# OV7725.net
KiCad netlist of a schematic drawn in EAGLE
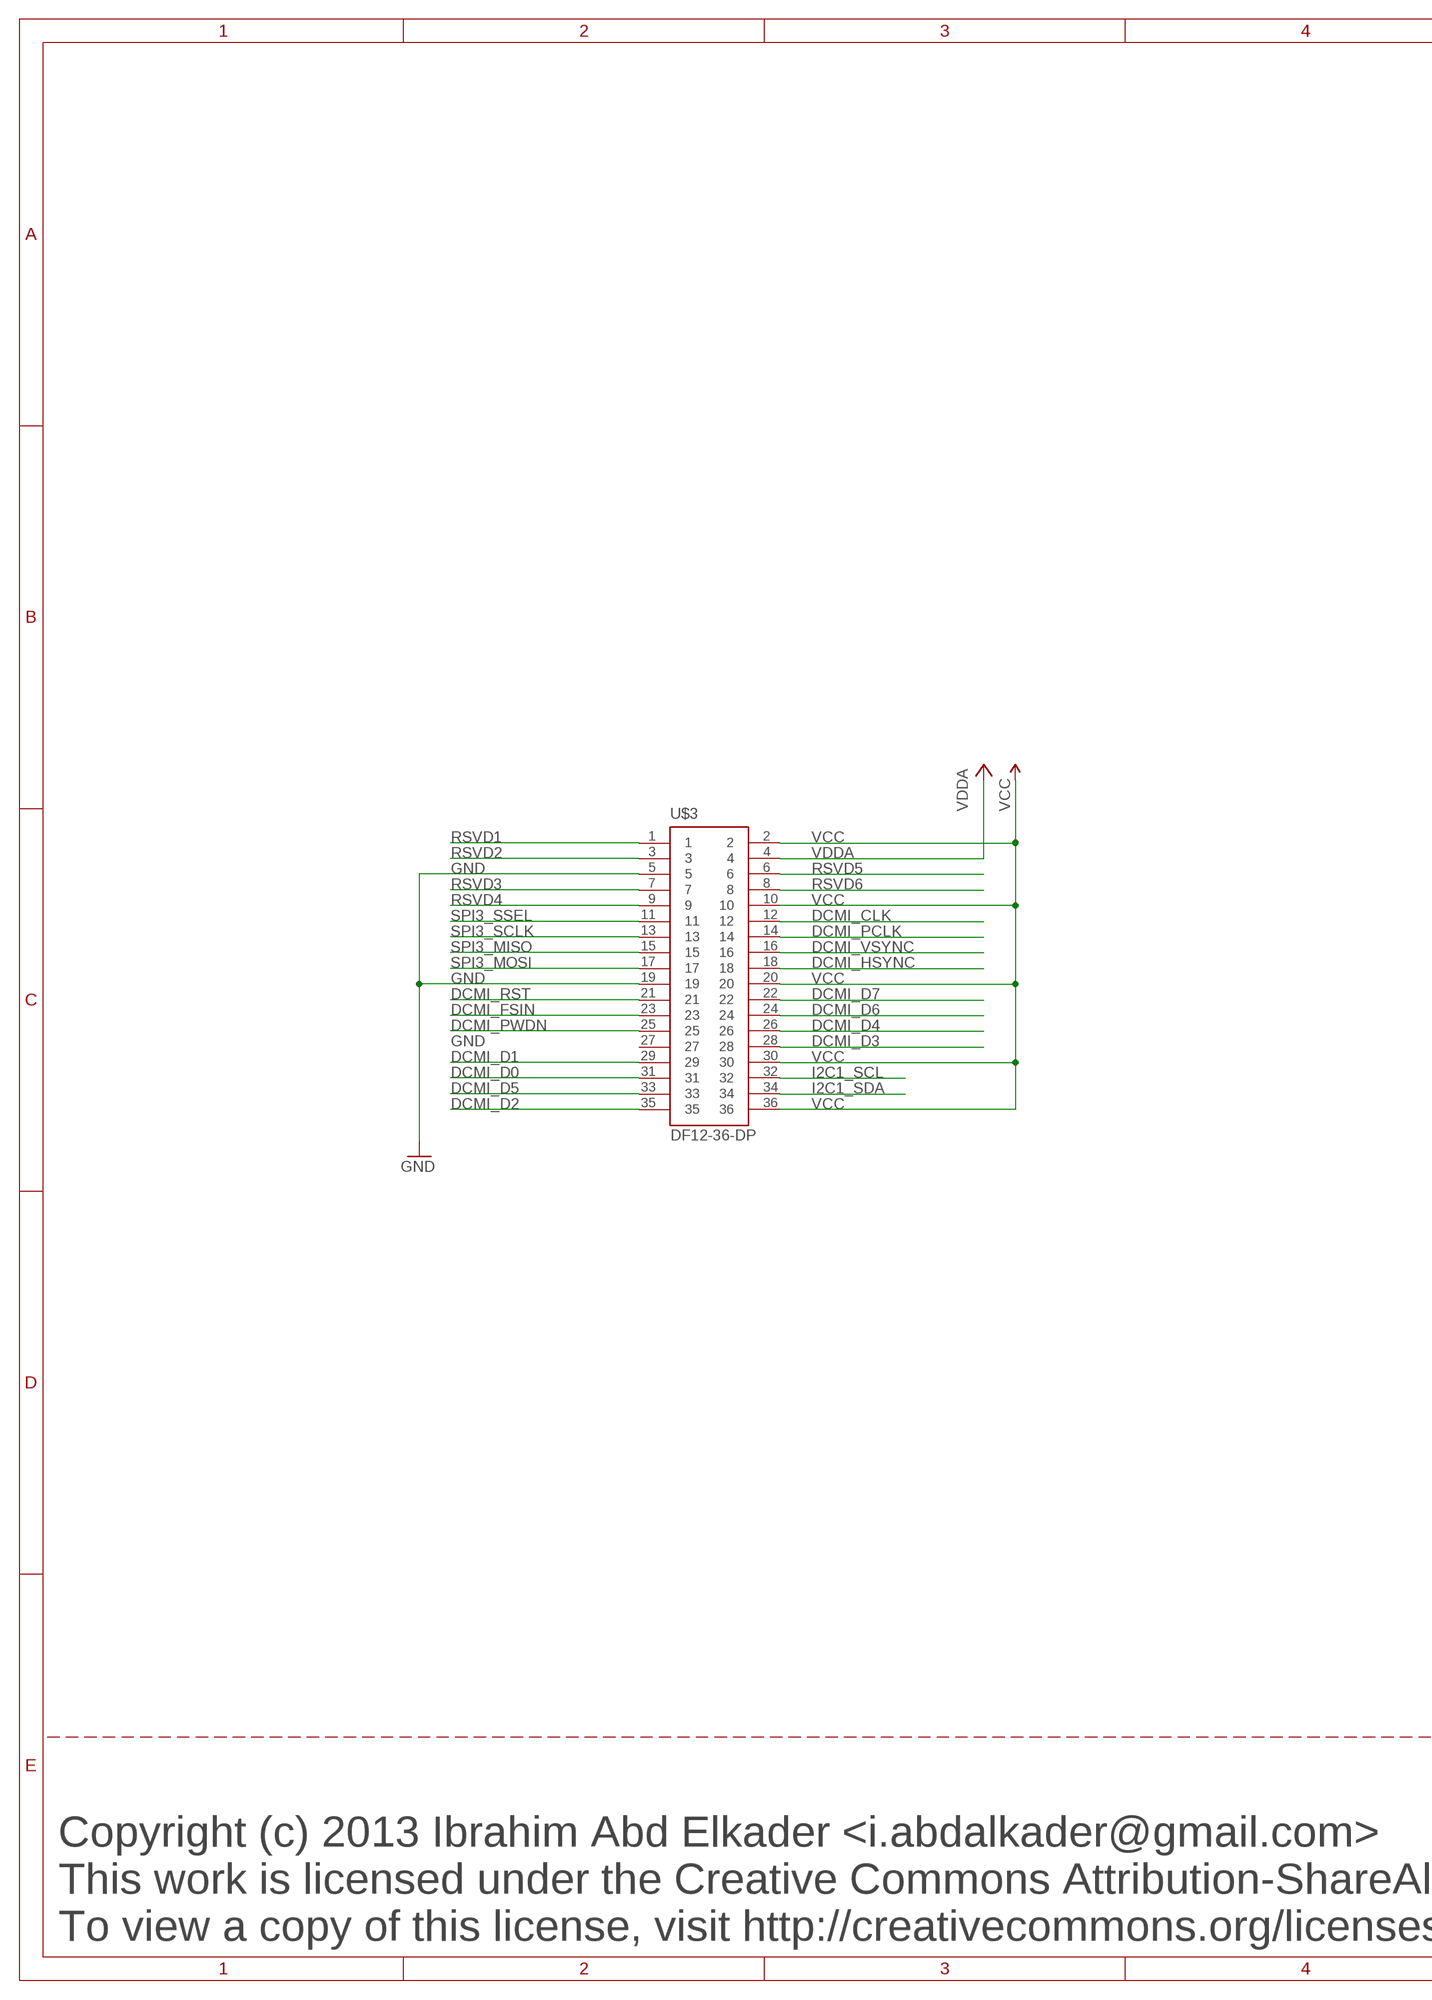
[diagram p0: schematic, sheet 1, part 1 of 2]
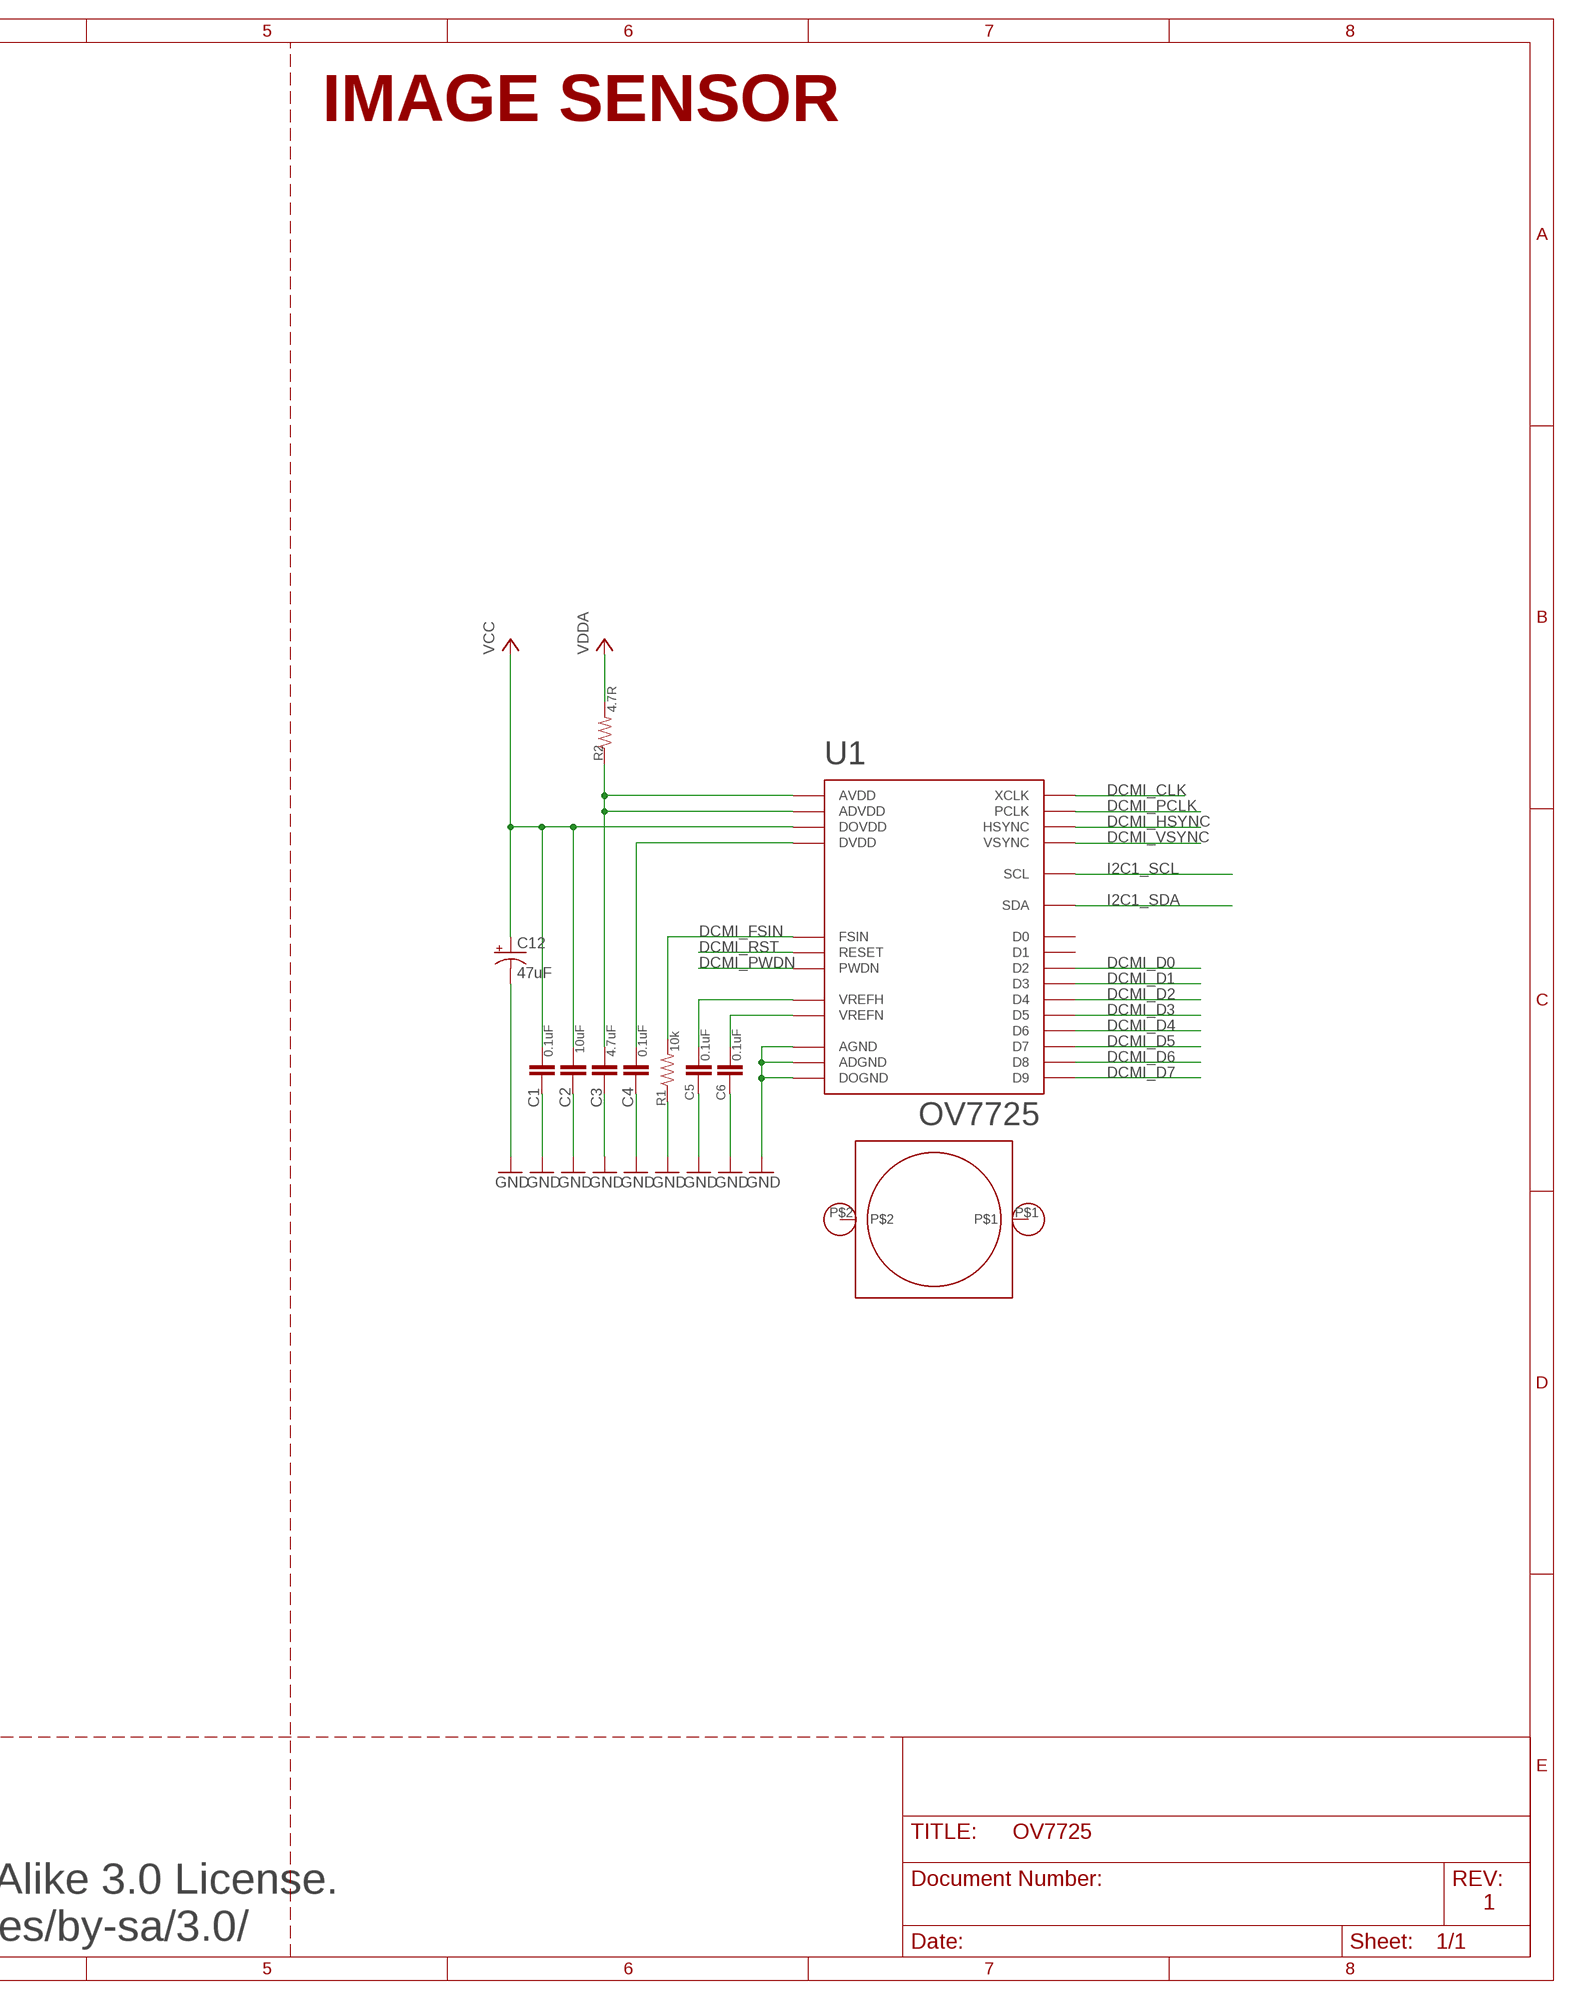
[diagram p1: schematic, sheet 1, part 2 of 2]

(export (version "E")
  (design (tool "Eeschema 10.0.6"))
  (components
    (comp (ref "C1")
      (value "0.1uF")
      (footprint "eagle-import:0603-CAP")
      (libsource (lib "eagle-import") (part "CAP0603-CAP"))
    )
    (comp (ref "C2")
      (value "10uF")
      (footprint "eagle-import:0805")
      (libsource (lib "eagle-import") (part "CAP0805"))
    )
    (comp (ref "C3")
      (value "4.7uF")
      (footprint "eagle-import:0603-CAP")
      (libsource (lib "eagle-import") (part "CAP0603-CAP"))
    )
    (comp (ref "C4")
      (value "0.1uF")
      (footprint "eagle-import:0603-CAP")
      (libsource (lib "eagle-import") (part "CAP0603-CAP"))
    )
    (comp (ref "C5")
      (value "0.1uF")
      (footprint "eagle-import:0603-CAP")
      (libsource (lib "eagle-import") (part "CAP0603-CAP"))
    )
    (comp (ref "C6")
      (value "0.1uF")
      (footprint "eagle-import:0603-CAP")
      (libsource (lib "eagle-import") (part "CAP0603-CAP"))
    )
    (comp (ref "C12")
      (value "47uF")
      (footprint "eagle-import:EIA3216")
      (libsource (lib "eagle-import") (part "CAP_POL1206"))
    )
    (comp (ref "LM1")
      (value "LENSMOUNT20MM")
      (footprint "eagle-import:LENSMOUNT-20MM")
      (libsource (lib "eagle-import") (part "LENSMOUNT20MM"))
    )
    (comp (ref "R1")
      (value "10k")
      (footprint "eagle-import:0603-RES")
      (libsource (lib "eagle-import") (part "RESISTOR0603-RES"))
    )
    (comp (ref "R2")
      (value "4.7R")
      (footprint "eagle-import:0603-RES")
      (libsource (lib "eagle-import") (part "RESISTOR0603-RES"))
    )
    (comp (ref "U$3")
      (value "DF12-36-DP")
      (footprint "eagle-import:DF12-36-DP")
      (libsource (lib "eagle-import") (part "DF12-36-DP"))
    )
    (comp (ref "U1")
      (value "OV7725")
      (footprint "eagle-import:CSP2-28")
      (libsource (lib "eagle-import") (part "OV7725"))
    )
  )
  (nets
    (net (code "1") (name "/DCMI_CLK") (class "Default")
      (node (ref "U$3") (pin "12") (pinfunction "12_12") (pintype "bidirectional"))
      (node (ref "U1") (pin "F3") (pinfunction "XCLK_F3") (pintype "bidirectional"))
    )
    (net (code "2") (name "/DCMI_D0") (class "Default")
      (node (ref "U$3") (pin "31") (pinfunction "31_31") (pintype "bidirectional"))
      (node (ref "U1") (pin "F5") (pinfunction "D2_F5") (pintype "bidirectional"))
    )
    (net (code "3") (name "/DCMI_D1") (class "Default")
      (node (ref "U$3") (pin "29") (pinfunction "29_29") (pintype "bidirectional"))
      (node (ref "U1") (pin "F2") (pinfunction "D3_F2") (pintype "bidirectional"))
    )
    (net (code "4") (name "/DCMI_D2") (class "Default")
      (node (ref "U$3") (pin "35") (pinfunction "35_35") (pintype "bidirectional"))
      (node (ref "U1") (pin "D6") (pinfunction "D4_D6") (pintype "bidirectional"))
    )
    (net (code "5") (name "/DCMI_D3") (class "Default")
      (node (ref "U$3") (pin "28") (pinfunction "28_28") (pintype "bidirectional"))
      (node (ref "U1") (pin "D1") (pinfunction "D5_D1") (pintype "bidirectional"))
    )
    (net (code "6") (name "/DCMI_D4") (class "Default")
      (node (ref "U$3") (pin "26") (pinfunction "26_26") (pintype "bidirectional"))
      (node (ref "U1") (pin "E6") (pinfunction "D6_E6") (pintype "bidirectional"))
    )
    (net (code "7") (name "/DCMI_D5") (class "Default")
      (node (ref "U$3") (pin "33") (pinfunction "33_33") (pintype "bidirectional"))
      (node (ref "U1") (pin "E1") (pinfunction "D7_E1") (pintype "bidirectional"))
    )
    (net (code "8") (name "/DCMI_D6") (class "Default")
      (node (ref "U$3") (pin "24") (pinfunction "24_24") (pintype "bidirectional"))
      (node (ref "U1") (pin "F6") (pinfunction "D8_F6") (pintype "bidirectional"))
    )
    (net (code "9") (name "/DCMI_D7") (class "Default")
      (node (ref "U$3") (pin "22") (pinfunction "22_22") (pintype "bidirectional"))
      (node (ref "U1") (pin "F1") (pinfunction "D9_F1") (pintype "bidirectional"))
    )
    (net (code "10") (name "/DCMI_FSIN") (class "Default")
      (node (ref "R1") (pin "2") (pinfunction "2_2") (pintype "passive"))
      (node (ref "U$3") (pin "23") (pinfunction "23_23") (pintype "bidirectional"))
      (node (ref "U1") (pin "A4") (pinfunction "FSIN_A4") (pintype "input"))
    )
    (net (code "11") (name "/DCMI_HSYNC") (class "Default")
      (node (ref "U$3") (pin "18") (pinfunction "18_18") (pintype "bidirectional"))
      (node (ref "U1") (pin "B6") (pinfunction "HSYNC_B6") (pintype "bidirectional"))
    )
    (net (code "12") (name "/DCMI_PCLK") (class "Default")
      (node (ref "U$3") (pin "14") (pinfunction "14_14") (pintype "bidirectional"))
      (node (ref "U1") (pin "E4") (pinfunction "PCLK_E4") (pintype "bidirectional"))
    )
    (net (code "13") (name "/DCMI_PWDN") (class "Default")
      (node (ref "U$3") (pin "25") (pinfunction "25_25") (pintype "bidirectional"))
      (node (ref "U1") (pin "C1") (pinfunction "PWDN_C1") (pintype "bidirectional"))
    )
    (net (code "14") (name "/DCMI_RST") (class "Default")
      (node (ref "U$3") (pin "21") (pinfunction "21_21") (pintype "bidirectional"))
      (node (ref "U1") (pin "A2") (pinfunction "RESET_A2") (pintype "bidirectional"))
    )
    (net (code "15") (name "/DCMI_VSYNC") (class "Default")
      (node (ref "U$3") (pin "16") (pinfunction "16_16") (pintype "bidirectional"))
      (node (ref "U1") (pin "C6") (pinfunction "VSYNC_C6") (pintype "bidirectional"))
    )
    (net (code "16") (name "/I2C1_SCL") (class "Default")
      (node (ref "U$3") (pin "32") (pinfunction "32_32") (pintype "bidirectional"))
      (node (ref "U1") (pin "A5") (pinfunction "SCL_A5") (pintype "bidirectional"))
    )
    (net (code "17") (name "/I2C1_SDA") (class "Default")
      (node (ref "U$3") (pin "34") (pinfunction "34_34") (pintype "bidirectional"))
      (node (ref "U1") (pin "B5") (pinfunction "SDA_B5") (pintype "bidirectional"))
    )
    (net (code "18") (name "/P$1") (class "Default")
      (node (ref "LM1") (pin "P$1") (pinfunction "P$1_P$1") (pintype "power_in"))
    )
    (net (code "19") (name "/P$2") (class "Default")
      (node (ref "LM1") (pin "P$2") (pinfunction "P$2_P$2") (pintype "power_in"))
    )
    (net (code "20") (name "/RSVD1") (class "Default")
      (node (ref "U$3") (pin "1") (pinfunction "1_1") (pintype "bidirectional"))
    )
    (net (code "21") (name "/RSVD2") (class "Default")
      (node (ref "U$3") (pin "3") (pinfunction "3_3") (pintype "bidirectional"))
    )
    (net (code "22") (name "/RSVD3") (class "Default")
      (node (ref "U$3") (pin "7") (pinfunction "7_7") (pintype "bidirectional"))
    )
    (net (code "23") (name "/RSVD4") (class "Default")
      (node (ref "U$3") (pin "9") (pinfunction "9_9") (pintype "bidirectional"))
    )
    (net (code "24") (name "/RSVD5") (class "Default")
      (node (ref "U$3") (pin "6") (pinfunction "6_6") (pintype "bidirectional"))
    )
    (net (code "25") (name "/RSVD6") (class "Default")
      (node (ref "U$3") (pin "8") (pinfunction "8_8") (pintype "bidirectional"))
    )
    (net (code "26") (name "/SPI3_MISO") (class "Default")
      (node (ref "U$3") (pin "15") (pinfunction "15_15") (pintype "bidirectional"))
    )
    (net (code "27") (name "/SPI3_MOSI") (class "Default")
      (node (ref "U$3") (pin "17") (pinfunction "17_17") (pintype "bidirectional"))
    )
    (net (code "28") (name "/SPI3_SCLK") (class "Default")
      (node (ref "U$3") (pin "13") (pinfunction "13_13") (pintype "bidirectional"))
    )
    (net (code "29") (name "/SPI3_SSEL") (class "Default")
      (node (ref "U$3") (pin "11") (pinfunction "11_11") (pintype "bidirectional"))
    )
    (net (code "30") (name "GND") (class "Default")
      (node (ref "C1") (pin "2") (pinfunction "2_2") (pintype "passive"))
      (node (ref "C12") (pin "C") (pinfunction "-_C") (pintype "passive"))
      (node (ref "C2") (pin "2") (pinfunction "2_2") (pintype "passive"))
      (node (ref "C3") (pin "2") (pinfunction "2_2") (pintype "passive"))
      (node (ref "C4") (pin "2") (pinfunction "2_2") (pintype "passive"))
      (node (ref "C5") (pin "2") (pinfunction "2_2") (pintype "passive"))
      (node (ref "C6") (pin "2") (pinfunction "2_2") (pintype "passive"))
      (node (ref "R1") (pin "1") (pinfunction "1_1") (pintype "passive"))
      (node (ref "U$3") (pin "19") (pinfunction "19_19") (pintype "bidirectional"))
      (node (ref "U$3") (pin "5") (pinfunction "5_5") (pintype "bidirectional"))
      (node (ref "U1") (pin "B1") (pinfunction "ADGND_B1") (pintype "power_in"))
      (node (ref "U1") (pin "B4") (pinfunction "AGND_B4") (pintype "power_in"))
      (node (ref "U1") (pin "F4") (pinfunction "DOGND_F4") (pintype "power_in"))
    )
    (net (code "31") (name "Net-(U1-ADVDD)") (class "Default")
      (node (ref "C3") (pin "1") (pinfunction "1_1") (pintype "passive"))
      (node (ref "R2") (pin "1") (pinfunction "1_1") (pintype "passive"))
      (node (ref "U1") (pin "A1") (pinfunction "ADVDD_A1") (pintype "power_in"))
      (node (ref "U1") (pin "B3") (pinfunction "AVDD_B3") (pintype "power_in"))
    )
    (net (code "32") (name "Net-(U1-DVDD)") (class "Default")
      (node (ref "C4") (pin "1") (pinfunction "1_1") (pintype "passive"))
      (node (ref "U1") (pin "E3") (pinfunction "DVDD_E3") (pintype "power_in"))
    )
    (net (code "33") (name "Net-(U1-VREFH)") (class "Default")
      (node (ref "C5") (pin "1") (pinfunction "1_1") (pintype "passive"))
      (node (ref "U1") (pin "A3") (pinfunction "VREFH_A3") (pintype "power_in"))
    )
    (net (code "34") (name "Net-(U1-VREFN)") (class "Default")
      (node (ref "C6") (pin "1") (pinfunction "1_1") (pintype "passive"))
      (node (ref "U1") (pin "B2") (pinfunction "VREFN_B2") (pintype "power_in"))
    )
    (net (code "35") (name "VCC") (class "Default")
      (node (ref "C1") (pin "1") (pinfunction "1_1") (pintype "passive"))
      (node (ref "C12") (pin "A") (pinfunction "+_A") (pintype "passive"))
      (node (ref "C2") (pin "1") (pinfunction "1_1") (pintype "passive"))
      (node (ref "U$3") (pin "10") (pinfunction "10_10") (pintype "bidirectional"))
      (node (ref "U$3") (pin "2") (pinfunction "2_2") (pintype "bidirectional"))
      (node (ref "U$3") (pin "20") (pinfunction "20_20") (pintype "bidirectional"))
      (node (ref "U$3") (pin "30") (pinfunction "30_30") (pintype "bidirectional"))
      (node (ref "U$3") (pin "36") (pinfunction "36_36") (pintype "bidirectional"))
      (node (ref "U1") (pin "E5") (pinfunction "DOVDD_E5") (pintype "power_in"))
    )
    (net (code "36") (name "VDDA") (class "Default")
      (node (ref "R2") (pin "2") (pinfunction "2_2") (pintype "passive"))
      (node (ref "U$3") (pin "4") (pinfunction "4_4") (pintype "bidirectional"))
    )
    (net (code "37") (name "unconnected-(U$3-Pad27)") (class "Default")
      (node (ref "U$3") (pin "27") (pinfunction "27_27") (pintype "bidirectional"))
    )
    (net (code "38") (name "unconnected-(U1-D0-PadA6)") (class "Default")
      (node (ref "U1") (pin "A6") (pinfunction "D0_A6") (pintype "bidirectional"))
    )
    (net (code "39") (name "unconnected-(U1-D1-PadE2)") (class "Default")
      (node (ref "U1") (pin "E2") (pinfunction "D1_E2") (pintype "bidirectional"))
    )
  )
)
